# WaterLevel-Eagle-V1.net
KiCad netlist of a schematic drawn in EAGLE
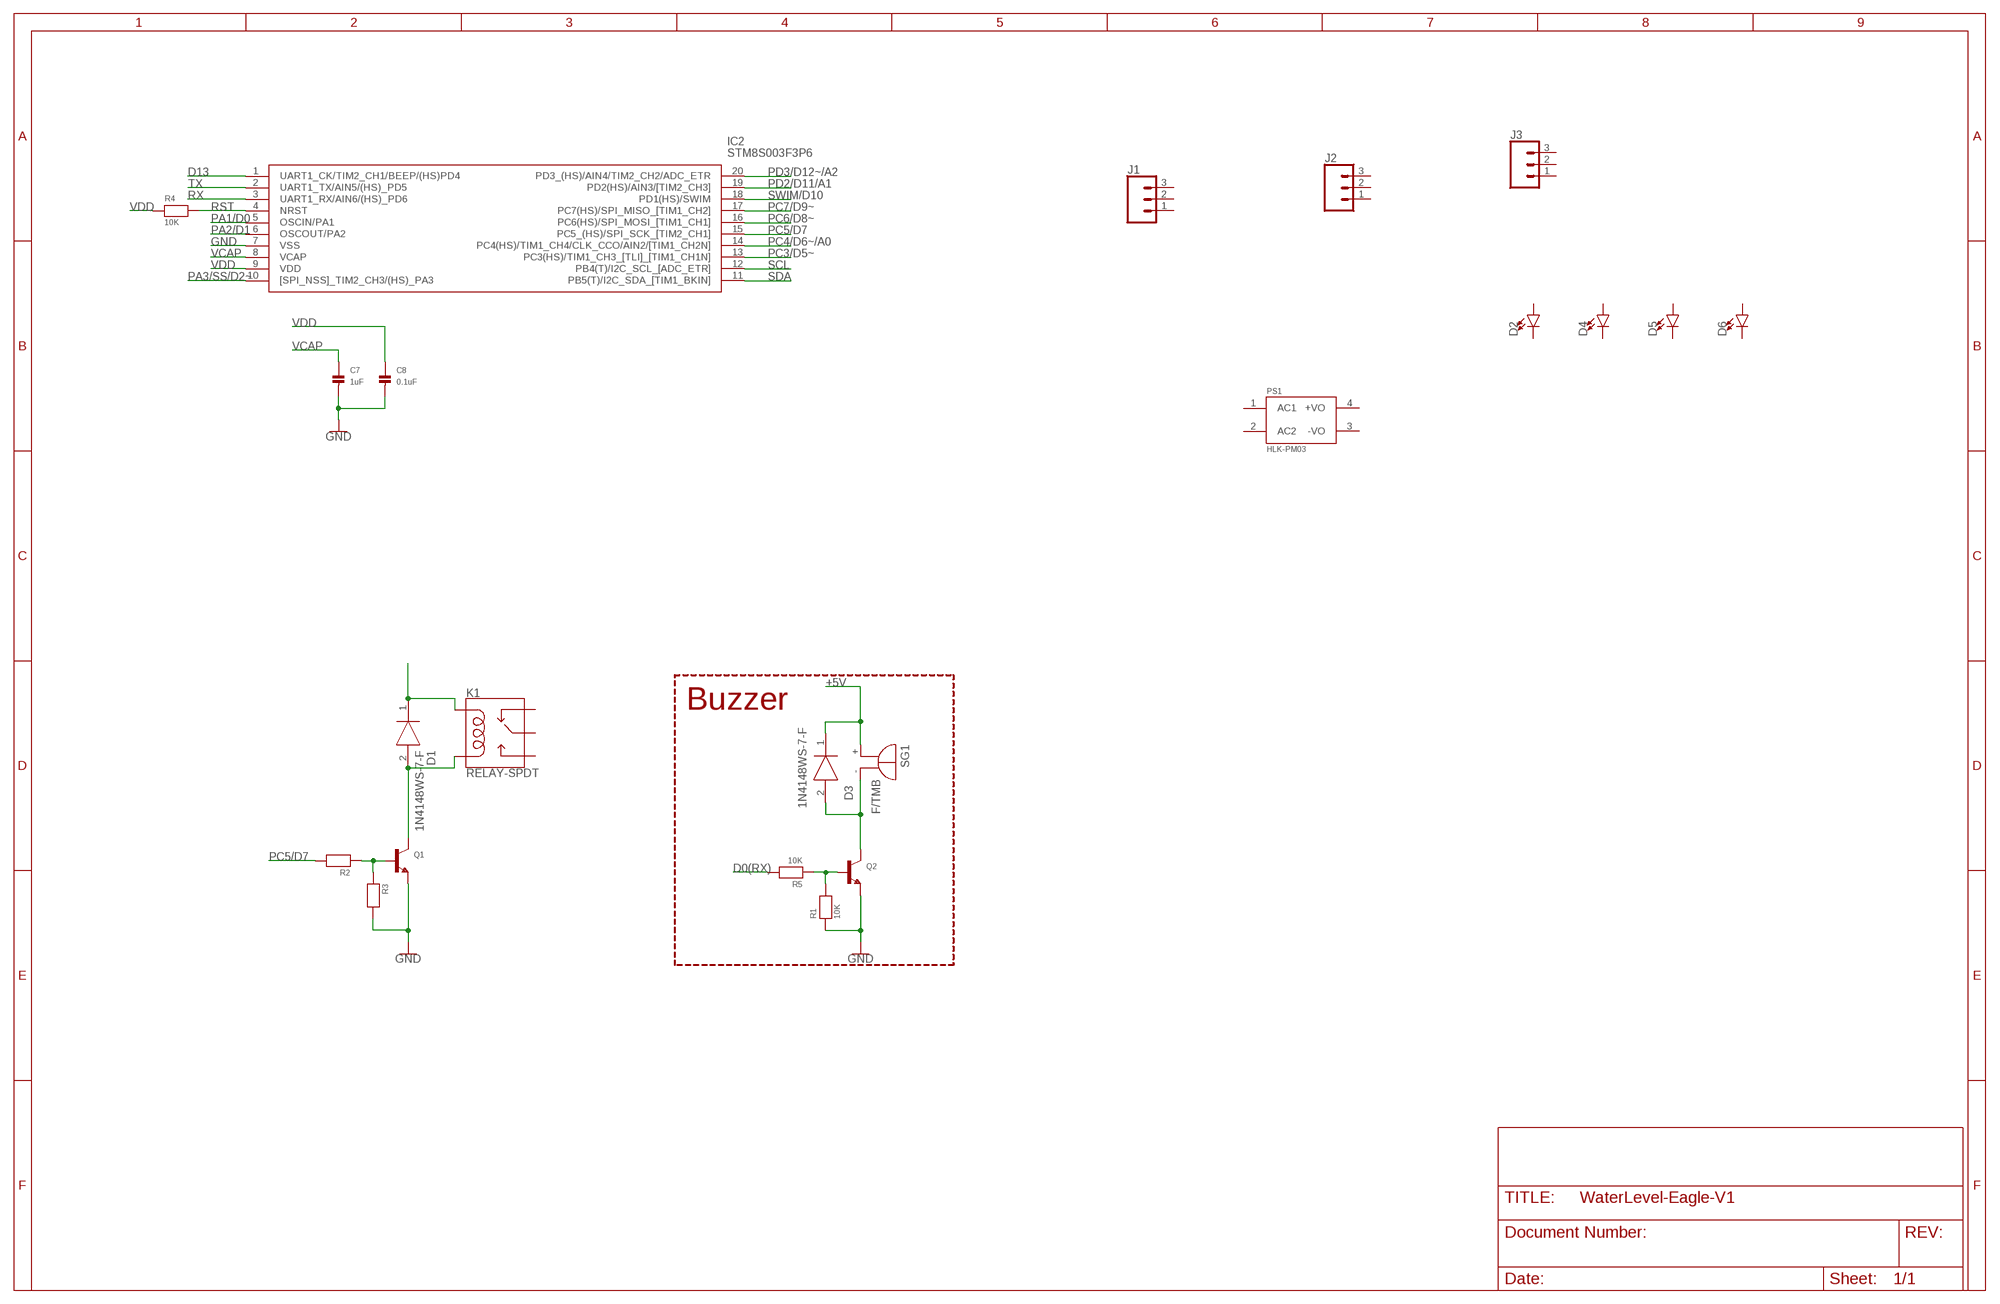
[diagram p0: schematic, sheet 1]

(export (version "E")
  (design (tool "Eeschema 10.0.6"))
  (components
    (comp (ref "C7")
      (value "1uF")
      (footprint "eagle-import:C0805")
      (libsource (lib "eagle-import") (part "CAP_CERAMIC0805"))
    )
    (comp (ref "C8")
      (value "0.1uF")
      (footprint "eagle-import:C0805")
      (libsource (lib "eagle-import") (part "CAP_CERAMIC0805"))
    )
    (comp (ref "D1")
      (value "1N4148WS-7-F")
      (footprint "eagle-import:SOD2513X120N")
      (fields (field (name "MOUSER_PART_NUMBER") "621-1N4148WS-F"))
      (libsource (lib "eagle-import") (part "1N4148WS-7-F"))
    )
    (comp (ref "D2")
      (value "LED-5MM-REC5MM")
      (footprint "eagle-import:LED_5MM")
      (libsource (lib "eagle-import") (part "LED-5MM-REC5MM"))
    )
    (comp (ref "D3")
      (value "1N4148WS-7-F")
      (footprint "eagle-import:SOD2513X120N")
      (fields (field (name "MOUSER_PART_NUMBER") "621-1N4148WS-F"))
      (libsource (lib "eagle-import") (part "1N4148WS-7-F"))
    )
    (comp (ref "D4")
      (value "LED-5MM-REC5MM")
      (footprint "eagle-import:LED_5MM")
      (libsource (lib "eagle-import") (part "LED-5MM-REC5MM"))
    )
    (comp (ref "D5")
      (value "LED-5MM-REC5MM")
      (footprint "eagle-import:LED_5MM")
      (libsource (lib "eagle-import") (part "LED-5MM-REC5MM"))
    )
    (comp (ref "D6")
      (value "LED-5MM-REC5MM")
      (footprint "eagle-import:LED_5MM")
      (libsource (lib "eagle-import") (part "LED-5MM-REC5MM"))
    )
    (comp (ref "IC2")
      (value "STM8S003F3P6")
      (footprint "eagle-import:SOP65P640X120-20N")
      (fields (field (name "MOUSER_PART_NUMBER") "511-STM8S003F3P6"))
      (libsource (lib "eagle-import") (part "STM8S003F3P6"))
    )
    (comp (ref "J1")
      (value "SCREW-CONN_03-SCREW-5MM")
      (footprint "eagle-import:SCREWTERMINAL-5MM-3")
      (libsource (lib "eagle-import") (part "SCREW-CONN_03-SCREW-5MM"))
    )
    (comp (ref "J2")
      (value "SCREW-CONN_03-SCREW-5MM")
      (footprint "eagle-import:SCREWTERMINAL-5MM-3")
      (libsource (lib "eagle-import") (part "SCREW-CONN_03-SCREW-5MM"))
    )
    (comp (ref "J3")
      (value "SCREW-CONN_03-SCREW-5MM")
      (footprint "eagle-import:SCREWTERMINAL-5MM-3")
      (libsource (lib "eagle-import") (part "SCREW-CONN_03-SCREW-5MM"))
    )
    (comp (ref "K1")
      (value "RELAY-SPDT")
      (footprint "eagle-import:RELAY_G5LE")
      (libsource (lib "eagle-import") (part "RELAY-SPDT"))
    )
    (comp (ref "PS1")
      (value "HLK-PM03")
      (footprint "eagle-import:CONV_HLK-PM03")
      (fields (field (name "MF") "Hi-link"))
      (libsource (lib "eagle-import") (part "HLK-PM03"))
    )
    (comp (ref "Q1")
      (value "TRANSISTOR_NPNWIDE")
      (footprint "eagle-import:SOT23-WIDE")
      (libsource (lib "eagle-import") (part "TRANSISTOR_NPNWIDE"))
    )
    (comp (ref "Q2")
      (value "TRANSISTOR_NPNWIDE")
      (footprint "eagle-import:SOT23-WIDE")
      (libsource (lib "eagle-import") (part "TRANSISTOR_NPNWIDE"))
    )
    (comp (ref "R1")
      (value "10K")
      (footprint "eagle-import:R0603")
      (libsource (lib "eagle-import") (part "RESISTOR0603"))
    )
    (comp (ref "R2")
      (value "RESISTOR0805")
      (footprint "eagle-import:R0805")
      (libsource (lib "eagle-import") (part "RESISTOR0805"))
    )
    (comp (ref "R3")
      (value "RESISTOR0805")
      (footprint "eagle-import:R0805")
      (libsource (lib "eagle-import") (part "RESISTOR0805"))
    )
    (comp (ref "R4")
      (value "10K")
      (footprint "eagle-import:R0805")
      (libsource (lib "eagle-import") (part "RESISTOR0805"))
    )
    (comp (ref "R5")
      (value "10K")
      (footprint "eagle-import:R0603")
      (libsource (lib "eagle-import") (part "RESISTOR0603"))
    )
    (comp (ref "SG1")
      (value "F/TMB")
      (footprint "eagle-import:F_TMB")
      (libsource (lib "eagle-import") (part "F/TMB"))
    )
  )
  (nets
    (net (code "1") (name "/+5V") (class "Default")
      (node (ref "D3") (pin "1") (pinfunction "K_1") (pintype "bidirectional"))
      (node (ref "SG1") (pin "+") (pinfunction "+_+") (pintype "passive"))
    )
    (net (code "2") (name "/D0(RX)") (class "Default")
      (node (ref "R5") (pin "2") (pinfunction "2_2") (pintype "passive"))
    )
    (net (code "3") (name "/D13") (class "Default")
      (node (ref "IC2") (pin "1") (pinfunction "UART1_CK/TIM2_CH1/BEEP/(HS)PD4_1") (pintype "bidirectional"))
    )
    (net (code "4") (name "/PA1{slash}D0") (class "Default")
      (node (ref "IC2") (pin "5") (pinfunction "OSCIN/PA1_5") (pintype "input"))
    )
    (net (code "5") (name "/PA2{slash}D1") (class "Default")
      (node (ref "IC2") (pin "6") (pinfunction "OSCOUT/PA2_6") (pintype "output"))
    )
    (net (code "6") (name "/PA3{slash}SS{slash}D2~{}") (class "Default")
      (node (ref "IC2") (pin "10") (pinfunction "[SPI_NSS]_TIM2_CH3/(HS)_PA3_10") (pintype "bidirectional"))
    )
    (net (code "7") (name "/PC3{slash}D5~{}") (class "Default")
      (node (ref "IC2") (pin "13") (pinfunction "PC3(HS)/TIM1_CH3_[TLI]_[TIM1_CH1N]_13") (pintype "bidirectional"))
    )
    (net (code "8") (name "/PC4{slash}D6~{{slash}A0}") (class "Default")
      (node (ref "IC2") (pin "14") (pinfunction "PC4(HS)/TIM1_CH4/CLK_CCO/AIN2/[TIM1_CH2N]_14") (pintype "input"))
    )
    (net (code "9") (name "/PC5{slash}D7") (class "Default")
      (node (ref "IC2") (pin "15") (pinfunction "PC5_(HS)/SPI_SCK_[TIM2_CH1]_15") (pintype "bidirectional"))
      (node (ref "R2") (pin "2") (pinfunction "2_2") (pintype "passive"))
    )
    (net (code "10") (name "/PC6{slash}D8~{}") (class "Default")
      (node (ref "IC2") (pin "16") (pinfunction "PC6(HS)/SPI_MOSI_[TIM1_CH1]_16") (pintype "bidirectional"))
    )
    (net (code "11") (name "/PC7{slash}D9~{}") (class "Default")
      (node (ref "IC2") (pin "17") (pinfunction "PC7(HS)/SPI_MISO_[TIM1_CH2]_17") (pintype "bidirectional"))
    )
    (net (code "12") (name "/PD2{slash}D11{slash}A1") (class "Default")
      (node (ref "IC2") (pin "19") (pinfunction "PD2(HS)/AIN3/[TIM2_CH3]_19") (pintype "input"))
    )
    (net (code "13") (name "/PD3{slash}D12~{{slash}A2}") (class "Default")
      (node (ref "IC2") (pin "20") (pinfunction "PD3_(HS)/AIN4/TIM2_CH2/ADC_ETR_20") (pintype "input"))
    )
    (net (code "14") (name "/RST") (class "Default")
      (node (ref "IC2") (pin "4") (pinfunction "NRST_4") (pintype "input"))
      (node (ref "R4") (pin "2") (pinfunction "2_2") (pintype "passive"))
    )
    (net (code "15") (name "/RX") (class "Default")
      (node (ref "IC2") (pin "3") (pinfunction "UART1_RX/AIN6/(HS)_PD6_3") (pintype "input"))
    )
    (net (code "16") (name "/SCL") (class "Default")
      (node (ref "IC2") (pin "12") (pinfunction "PB4(T)/I2C_SCL_[ADC_ETR]_12") (pintype "bidirectional"))
    )
    (net (code "17") (name "/SDA") (class "Default")
      (node (ref "IC2") (pin "11") (pinfunction "PB5(T)/I2C_SDA_[TIM1_BKIN]_11") (pintype "input"))
    )
    (net (code "18") (name "/SWIM{slash}D10") (class "Default")
      (node (ref "IC2") (pin "18") (pinfunction "PD1(HS)/SWIM_18") (pintype "bidirectional"))
    )
    (net (code "19") (name "/TX") (class "Default")
      (node (ref "IC2") (pin "2") (pinfunction "UART1_TX/AIN5/(HS)_PD5_2") (pintype "input"))
    )
    (net (code "20") (name "/VCAP") (class "Default")
      (node (ref "C7") (pin "1") (pinfunction "P$1_1") (pintype "passive"))
      (node (ref "IC2") (pin "8") (pinfunction "VCAP_8") (pintype "bidirectional"))
    )
    (net (code "21") (name "/VDD") (class "Default")
      (node (ref "C8") (pin "1") (pinfunction "P$1_1") (pintype "passive"))
      (node (ref "IC2") (pin "9") (pinfunction "VDD_9") (pintype "power_in"))
      (node (ref "R4") (pin "1") (pinfunction "1_1") (pintype "passive"))
    )
    (net (code "22") (name "GND") (class "Default")
      (node (ref "C7") (pin "2") (pinfunction "P$2_2") (pintype "passive"))
      (node (ref "C8") (pin "2") (pinfunction "P$2_2") (pintype "passive"))
      (node (ref "IC2") (pin "7") (pinfunction "VSS_7") (pintype "power_in"))
      (node (ref "Q1") (pin "2") (pinfunction "E_2") (pintype "passive"))
      (node (ref "Q2") (pin "2") (pinfunction "E_2") (pintype "passive"))
      (node (ref "R1") (pin "1") (pinfunction "1_1") (pintype "passive"))
      (node (ref "R3") (pin "2") (pinfunction "2_2") (pintype "passive"))
    )
    (net (code "23") (name "Net-(D1-A)") (class "Default")
      (node (ref "D1") (pin "2") (pinfunction "A_2") (pintype "bidirectional"))
      (node (ref "K1") (pin "5") (pinfunction "COIL2_5") (pintype "bidirectional"))
      (node (ref "Q1") (pin "3") (pinfunction "C_3") (pintype "passive"))
    )
    (net (code "24") (name "Net-(D1-K)") (class "Default")
      (node (ref "D1") (pin "1") (pinfunction "K_1") (pintype "bidirectional"))
      (node (ref "K1") (pin "2") (pinfunction "COIL1_2") (pintype "bidirectional"))
    )
    (net (code "25") (name "Net-(D3-A)") (class "Default")
      (node (ref "D3") (pin "2") (pinfunction "A_2") (pintype "bidirectional"))
      (node (ref "Q2") (pin "3") (pinfunction "C_3") (pintype "passive"))
      (node (ref "SG1") (pin "-") (pinfunction "-_-") (pintype "passive"))
    )
    (net (code "26") (name "Net-(Q1-B)") (class "Default")
      (node (ref "Q1") (pin "1") (pinfunction "B_1") (pintype "passive"))
      (node (ref "R2") (pin "1") (pinfunction "1_1") (pintype "passive"))
      (node (ref "R3") (pin "1") (pinfunction "1_1") (pintype "passive"))
    )
    (net (code "27") (name "Net-(Q2-B)") (class "Default")
      (node (ref "Q2") (pin "1") (pinfunction "B_1") (pintype "passive"))
      (node (ref "R1") (pin "2") (pinfunction "2_2") (pintype "passive"))
      (node (ref "R5") (pin "1") (pinfunction "1_1") (pintype "passive"))
    )
    (net (code "28") (name "unconnected-(D2-C-PadK)") (class "Default")
      (node (ref "D2") (pin "K") (pinfunction "C_K") (pintype "passive"))
    )
    (net (code "29") (name "unconnected-(D2-PadA)") (class "Default")
      (node (ref "D2") (pin "A") (pinfunction "A_A") (pintype "passive"))
    )
    (net (code "30") (name "unconnected-(D4-C-PadK)") (class "Default")
      (node (ref "D4") (pin "K") (pinfunction "C_K") (pintype "passive"))
    )
    (net (code "31") (name "unconnected-(D4-PadA)") (class "Default")
      (node (ref "D4") (pin "A") (pinfunction "A_A") (pintype "passive"))
    )
    (net (code "32") (name "unconnected-(D5-C-PadK)") (class "Default")
      (node (ref "D5") (pin "K") (pinfunction "C_K") (pintype "passive"))
    )
    (net (code "33") (name "unconnected-(D5-PadA)") (class "Default")
      (node (ref "D5") (pin "A") (pinfunction "A_A") (pintype "passive"))
    )
    (net (code "34") (name "unconnected-(D6-C-PadK)") (class "Default")
      (node (ref "D6") (pin "K") (pinfunction "C_K") (pintype "passive"))
    )
    (net (code "35") (name "unconnected-(D6-PadA)") (class "Default")
      (node (ref "D6") (pin "A") (pinfunction "A_A") (pintype "passive"))
    )
    (net (code "36") (name "unconnected-(J1-Pad1)") (class "Default")
      (node (ref "J1") (pin "1") (pinfunction "1_1") (pintype "passive"))
    )
    (net (code "37") (name "unconnected-(J1-Pad2)") (class "Default")
      (node (ref "J1") (pin "2") (pinfunction "2_2") (pintype "passive"))
    )
    (net (code "38") (name "unconnected-(J1-Pad3)") (class "Default")
      (node (ref "J1") (pin "3") (pinfunction "3_3") (pintype "passive"))
    )
    (net (code "39") (name "unconnected-(J2-Pad1)") (class "Default")
      (node (ref "J2") (pin "1") (pinfunction "1_1") (pintype "passive"))
    )
    (net (code "40") (name "unconnected-(J2-Pad2)") (class "Default")
      (node (ref "J2") (pin "2") (pinfunction "2_2") (pintype "passive"))
    )
    (net (code "41") (name "unconnected-(J2-Pad3)") (class "Default")
      (node (ref "J2") (pin "3") (pinfunction "3_3") (pintype "passive"))
    )
    (net (code "42") (name "unconnected-(J3-Pad1)") (class "Default")
      (node (ref "J3") (pin "1") (pinfunction "1_1") (pintype "passive"))
    )
    (net (code "43") (name "unconnected-(J3-Pad2)") (class "Default")
      (node (ref "J3") (pin "2") (pinfunction "2_2") (pintype "passive"))
    )
    (net (code "44") (name "unconnected-(J3-Pad3)") (class "Default")
      (node (ref "J3") (pin "3") (pinfunction "3_3") (pintype "passive"))
    )
    (net (code "45") (name "unconnected-(K1-MAIN-Pad1)") (class "Default")
      (node (ref "K1") (pin "1") (pinfunction "MAIN_1") (pintype "bidirectional"))
    )
    (net (code "46") (name "unconnected-(K1-NC-Pad4)") (class "Default")
      (node (ref "K1") (pin "4") (pinfunction "NC_4") (pintype "bidirectional"))
    )
    (net (code "47") (name "unconnected-(K1-NO-Pad3)") (class "Default")
      (node (ref "K1") (pin "3") (pinfunction "NO_3") (pintype "bidirectional"))
    )
    (net (code "48") (name "unconnected-(PS1-+VO-Pad4)") (class "Default")
      (node (ref "PS1") (pin "4") (pinfunction "+VO_4") (pintype "output"))
    )
    (net (code "49") (name "unconnected-(PS1--VO-Pad3)") (class "Default")
      (node (ref "PS1") (pin "3") (pinfunction "-VO_3") (pintype "output"))
    )
    (net (code "50") (name "unconnected-(PS1-AC1-Pad1)") (class "Default")
      (node (ref "PS1") (pin "1") (pinfunction "AC1_1") (pintype "input"))
    )
    (net (code "51") (name "unconnected-(PS1-AC2-Pad2)") (class "Default")
      (node (ref "PS1") (pin "2") (pinfunction "AC2_2") (pintype "input"))
    )
  )
)
